# Reefing-IO.net
KiCad netlist of a schematic drawn in Altium Designer
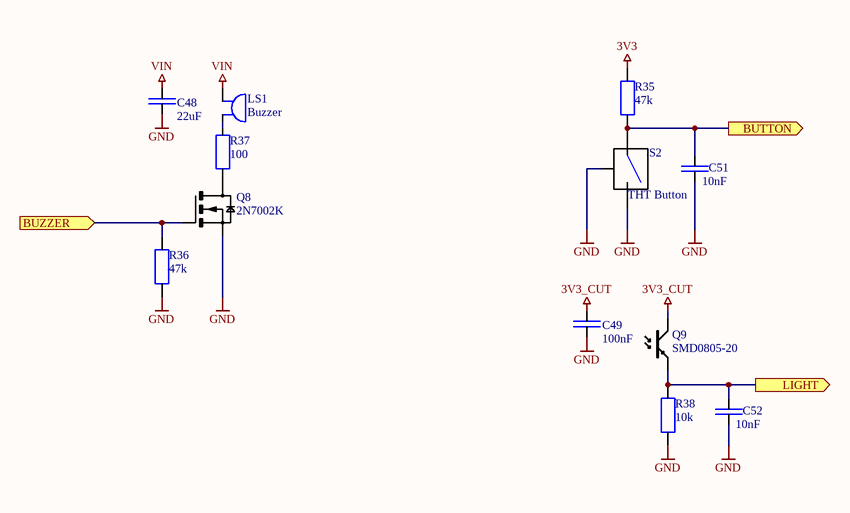
[diagram p0: Reefing-IO.SchDoc]

(export (version "E")
  (design (tool "Eeschema 10.0.6"))
  (components
    (comp (ref "C48")
      (value "22uF")
      (footprint "SMD Keramikkondensator 0805")
      (description "SMD Ceramic Capacitor E6")
      (libsource (lib "CATS-EUROC") (part "E6 - 22uF"))
    )
    (comp (ref "C49")
      (value "100nF")
      (footprint "SMD Keramikkondensator 0402")
      (description "SMD Ceramic Capacitor E6")
      (libsource (lib "CATS-EUROC") (part "E6 - 100nF"))
    )
    (comp (ref "C51")
      (value "10nF")
      (footprint "SMD Keramikkondensator 0402")
      (description "SMD Ceramic Capacitor E6")
      (libsource (lib "CATS-EUROC") (part "E6 - 10nF"))
    )
    (comp (ref "C52")
      (value "10nF")
      (footprint "SMD Keramikkondensator 0402")
      (description "SMD Ceramic Capacitor E6")
      (libsource (lib "CATS-EUROC") (part "E6 - 10nF"))
    )
    (comp (ref "LS1")
      (value "Buzzer")
      (footprint "SMD BUZZER CMT-8504")
      (description "Buzzers Indicator, Internally Driven Piezo 12V 10mA 3kHz 100dB @ 12V, 10cm Through Hole PC Pins")
      (libsource (lib "Other") (part "Buzzer"))
    )
    (comp (ref "Q8")
      (value "2N7002K")
      (footprint "SMD MOSFET SOT-23")
      (description "MOSFET N-Channel 60V / 500mA")
      (libsource (lib "Electronic Switches") (part "2N7002K"))
    )
    (comp (ref "Q9")
      (value "SMD0805-20")
      (footprint "SMD LED 0805")
      (libsource (lib "Sensors") (part "SMD0805-20"))
    )
    (comp (ref "R35")
      (value "47k")
      (footprint "SMD Widerstand 0402")
      (description "SMD Chip Resistor E24")
      (libsource (lib "Resistors-E24") (part "E24 - 47k"))
    )
    (comp (ref "R36")
      (value "47k")
      (footprint "SMD Widerstand 0402")
      (description "SMD Chip Resistor E24")
      (libsource (lib "") (part "E24 - 47k_1"))
    )
    (comp (ref "R37")
      (value "100")
      (footprint "SMD Widerstand 0805")
      (description "SMD Chip Resistor E24")
      (libsource (lib "CATS-EUROC") (part "E24 - 100"))
    )
    (comp (ref "R38")
      (value "10k")
      (footprint "SMD Widerstand 0402")
      (description "SMD Chip Resistor E24")
      (libsource (lib "CATS-EUROC") (part "E24 - 10k"))
    )
    (comp (ref "S2")
      (value "THT Button")
      (footprint "THT Button Right Angle")
      (description "Tactile Switch SPST-NO Side Actuated Through Hole, Right Angle")
      (libsource (lib "Switches") (part "Button SPST-NO Right Angle"))
    )
  )
  (nets
    (net (code "1") (name "/BUTTON") (class "Default")
      (node (ref "C51") (pin "2") (pinfunction "2_2") (pintype "passive"))
      (node (ref "R35") (pin "2") (pinfunction "2_2") (pintype "passive"))
      (node (ref "S2") (pin "2") (pinfunction "2_2") (pintype "passive"))
    )
    (net (code "2") (name "/BUZZER") (class "Default")
      (node (ref "Q8") (pin "G") (pinfunction "G_G") (pintype "passive"))
      (node (ref "R36") (pin "2") (pinfunction "2_2") (pintype "passive"))
    )
    (net (code "3") (name "/LIGHT") (class "Default")
      (node (ref "C52") (pin "2") (pinfunction "2_2") (pintype "passive"))
      (node (ref "Q9") (pin "K") (pinfunction "K_K") (pintype "passive"))
      (node (ref "R38") (pin "2") (pinfunction "2_2") (pintype "passive"))
    )
    (net (code "4") (name "3V3") (class "Default")
      (node (ref "R35") (pin "1") (pinfunction "1_1") (pintype "passive"))
    )
    (net (code "5") (name "3V3_CUT") (class "Default")
      (node (ref "C49") (pin "2") (pinfunction "2_2") (pintype "passive"))
      (node (ref "Q9") (pin "A") (pinfunction "A_A") (pintype "passive"))
    )
    (net (code "6") (name "GND") (class "Default")
      (node (ref "C48") (pin "1") (pinfunction "1_1") (pintype "passive"))
      (node (ref "C49") (pin "1") (pinfunction "1_1") (pintype "passive"))
      (node (ref "C51") (pin "1") (pinfunction "1_1") (pintype "passive"))
      (node (ref "C52") (pin "1") (pinfunction "1_1") (pintype "passive"))
      (node (ref "Q8") (pin "S") (pinfunction "S_S") (pintype "passive"))
      (node (ref "R36") (pin "1") (pinfunction "1_1") (pintype "passive"))
      (node (ref "R38") (pin "1") (pinfunction "1_1") (pintype "passive"))
      (node (ref "S2") (pin "1") (pinfunction "1_1") (pintype "passive"))
      (node (ref "S2") (pin "3") (pinfunction "3_3") (pintype "passive"))
    )
    (net (code "7") (name "Net-(LS1-Pad2)") (class "Default")
      (node (ref "LS1") (pin "2") (pinfunction "2_2") (pintype "passive"))
      (node (ref "R37") (pin "2") (pinfunction "2_2") (pintype "passive"))
    )
    (net (code "8") (name "Net-(Q8-PadD)") (class "Default")
      (node (ref "Q8") (pin "D") (pinfunction "D_D") (pintype "passive"))
      (node (ref "R37") (pin "1") (pinfunction "1_1") (pintype "passive"))
    )
    (net (code "9") (name "VIN") (class "Default")
      (node (ref "C48") (pin "2") (pinfunction "2_2") (pintype "passive"))
      (node (ref "LS1") (pin "1") (pinfunction "1_1") (pintype "passive"))
    )
  )
)
